# signal-a-1.net
KiCad netlist of a schematic drawn in EAGLE
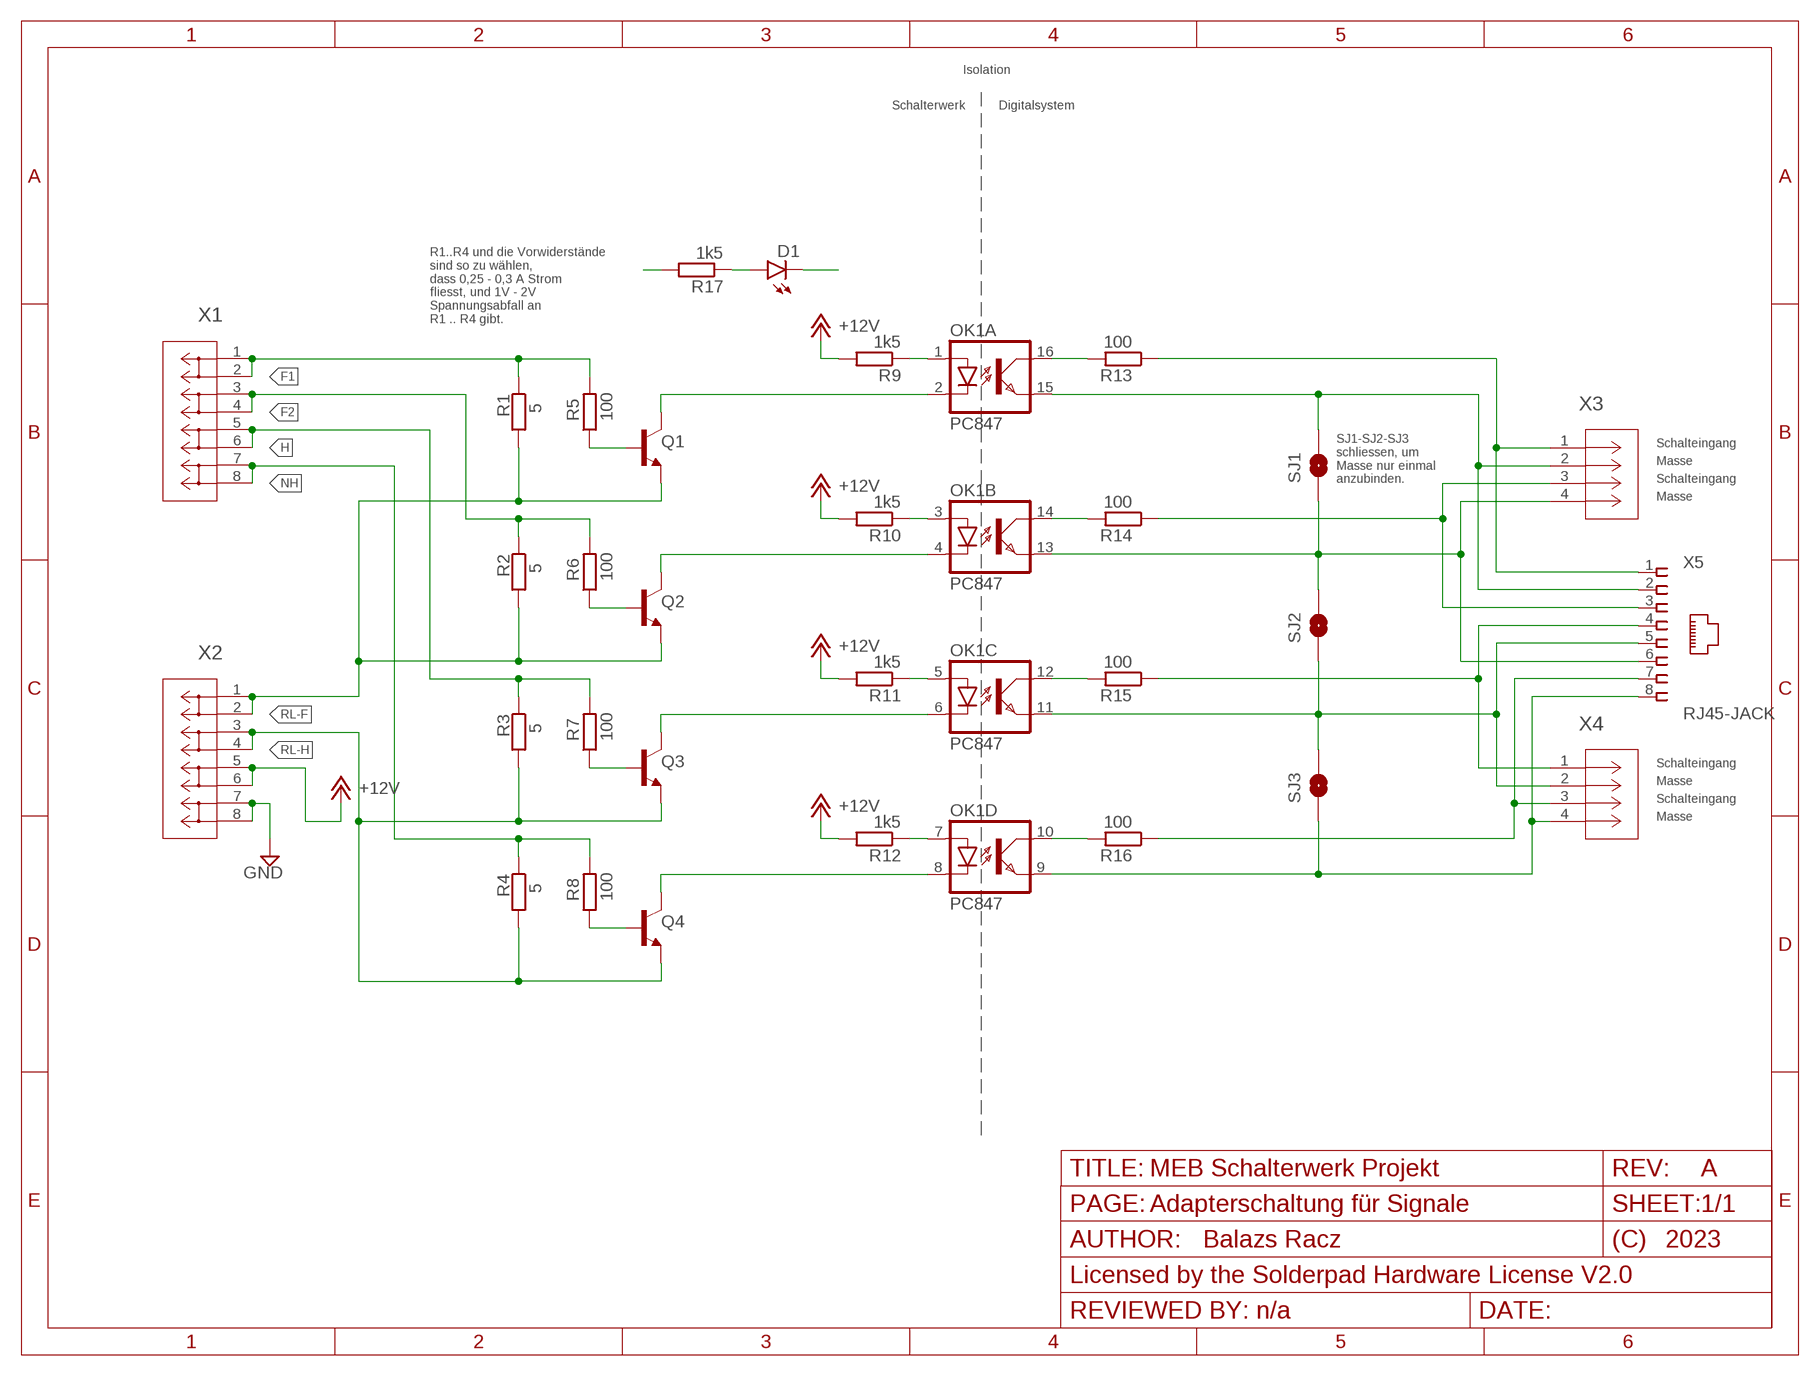
[diagram p0: schematic, sheet 1]

(export (version "E")
  (design (tool "Eeschema 10.0.6"))
  (components
    (comp (ref "D1")
      (value "LEDCHIPLED_0603")
      (footprint "eagle-import:CHIPLED_0603")
      (libsource (lib "eagle-import") (part "LEDCHIPLED_0603"))
    )
    (comp (ref "OK1")
      (value "PC847")
      (footprint "eagle-import:DIL16")
      (libsource (lib "eagle-import") (part "PC847"))
    )
    (comp (ref "Q1")
      (value "NPN-23")
      (footprint "eagle-import:SOT23")
      (libsource (lib "eagle-import") (part "NPN-23"))
    )
    (comp (ref "Q2")
      (value "NPN-23")
      (footprint "eagle-import:SOT23")
      (libsource (lib "eagle-import") (part "NPN-23"))
    )
    (comp (ref "Q3")
      (value "NPN-23")
      (footprint "eagle-import:SOT23")
      (libsource (lib "eagle-import") (part "NPN-23"))
    )
    (comp (ref "Q4")
      (value "NPN-23")
      (footprint "eagle-import:SOT23")
      (libsource (lib "eagle-import") (part "NPN-23"))
    )
    (comp (ref "R1")
      (value "5")
      (footprint "eagle-import:VTA52")
      (libsource (lib "eagle-import") (part "R-EU_VTA52"))
    )
    (comp (ref "R2")
      (value "5")
      (footprint "eagle-import:VTA52")
      (libsource (lib "eagle-import") (part "R-EU_VTA52"))
    )
    (comp (ref "R3")
      (value "5")
      (footprint "eagle-import:VTA52")
      (libsource (lib "eagle-import") (part "R-EU_VTA52"))
    )
    (comp (ref "R4")
      (value "5")
      (footprint "eagle-import:VTA52")
      (libsource (lib "eagle-import") (part "R-EU_VTA52"))
    )
    (comp (ref "R5")
      (value "100")
      (footprint "eagle-import:R0805")
      (libsource (lib "eagle-import") (part "R-EU_R0805"))
    )
    (comp (ref "R6")
      (value "100")
      (footprint "eagle-import:R0805")
      (libsource (lib "eagle-import") (part "R-EU_R0805"))
    )
    (comp (ref "R7")
      (value "100")
      (footprint "eagle-import:R0805")
      (libsource (lib "eagle-import") (part "R-EU_R0805"))
    )
    (comp (ref "R8")
      (value "100")
      (footprint "eagle-import:R0805")
      (libsource (lib "eagle-import") (part "R-EU_R0805"))
    )
    (comp (ref "R9")
      (value "1k5")
      (footprint "eagle-import:R0805")
      (libsource (lib "eagle-import") (part "R-EU_R0805"))
    )
    (comp (ref "R10")
      (value "1k5")
      (footprint "eagle-import:R0805")
      (libsource (lib "eagle-import") (part "R-EU_R0805"))
    )
    (comp (ref "R11")
      (value "1k5")
      (footprint "eagle-import:R0805")
      (libsource (lib "eagle-import") (part "R-EU_R0805"))
    )
    (comp (ref "R12")
      (value "1k5")
      (footprint "eagle-import:R0805")
      (libsource (lib "eagle-import") (part "R-EU_R0805"))
    )
    (comp (ref "R13")
      (value "100")
      (footprint "eagle-import:R0805")
      (libsource (lib "eagle-import") (part "R-EU_R0805"))
    )
    (comp (ref "R14")
      (value "100")
      (footprint "eagle-import:R0805")
      (libsource (lib "eagle-import") (part "R-EU_R0805"))
    )
    (comp (ref "R15")
      (value "100")
      (footprint "eagle-import:R0805")
      (libsource (lib "eagle-import") (part "R-EU_R0805"))
    )
    (comp (ref "R16")
      (value "100")
      (footprint "eagle-import:R0805")
      (libsource (lib "eagle-import") (part "R-EU_R0805"))
    )
    (comp (ref "R17")
      (value "1k5")
      (footprint "eagle-import:R0805")
      (libsource (lib "eagle-import") (part "R-EU_R0805"))
    )
    (comp (ref "SJ1")
      (value "SJRND2")
      (footprint "eagle-import:SJ_RND2")
      (libsource (lib "eagle-import") (part "SJRND2"))
    )
    (comp (ref "SJ2")
      (value "SJRND2")
      (footprint "eagle-import:SJ_RND2")
      (libsource (lib "eagle-import") (part "SJRND2"))
    )
    (comp (ref "SJ3")
      (value "SJRND2")
      (footprint "eagle-import:SJ_RND2")
      (libsource (lib "eagle-import") (part "SJRND2"))
    )
    (comp (ref "X1")
      (value "PHNX_4P_508CONN_1017493")
      (footprint "eagle-import:PHNX_4P_508")
      (fields
        (field (name "MANUFACTURER_PART_NUMBER") "1017505")
        (field (name "COPYRIGHT") "Copyright (C) 2023 Ultra Librarian. All rights reserved.")
      )
      (libsource (lib "eagle-import") (part "PHNX_4P_508CONN_1017493"))
    )
    (comp (ref "X2")
      (value "PHNX_4P_508CONN_1017493")
      (footprint "eagle-import:PHNX_4P_508")
      (fields
        (field (name "MANUFACTURER_PART_NUMBER") "1017505")
        (field (name "COPYRIGHT") "Copyright (C) 2023 Ultra Librarian. All rights reserved.")
      )
      (libsource (lib "eagle-import") (part "PHNX_4P_508CONN_1017493"))
    )
    (comp (ref "X3")
      (value "PHNX_4P_350CONN_1984989_PXC")
      (footprint "eagle-import:PHNX_4P_350")
      (fields
        (field (name "MANUFACTURER_PART_NUMBER") "1984989")
        (field (name "COPYRIGHT") "Copyright (C) 2023 Ultra Librarian. All rights reserved.")
      )
      (libsource (lib "eagle-import") (part "PHNX_4P_350CONN_1984989_PXC"))
    )
    (comp (ref "X4")
      (value "PHNX_4P_350CONN_1984989_PXC")
      (footprint "eagle-import:PHNX_4P_350")
      (fields
        (field (name "MANUFACTURER_PART_NUMBER") "1984989")
        (field (name "COPYRIGHT") "Copyright (C) 2023 Ultra Librarian. All rights reserved.")
      )
      (libsource (lib "eagle-import") (part "PHNX_4P_350CONN_1984989_PXC"))
    )
    (comp (ref "X5")
      (value "RJ45-JACK")
      (footprint "eagle-import:RJ45-PULSE-E5J88")
      (libsource (lib "eagle-import") (part "RJ45-JACKRJ45-PULSE-E5J00"))
    )
  )
  (nets
    (net (code "1") (name "+12V") (class "Default")
      (node (ref "R10") (pin "2") (pinfunction "2_2") (pintype "passive"))
      (node (ref "R11") (pin "2") (pinfunction "2_2") (pintype "passive"))
      (node (ref "R12") (pin "2") (pinfunction "2_2") (pintype "passive"))
      (node (ref "R9") (pin "2") (pinfunction "2_2") (pintype "passive"))
      (node (ref "X2") (pin "5") (pinfunction "5_5") (pintype "passive"))
      (node (ref "X2") (pin "6") (pinfunction "6_6") (pintype "passive"))
    )
    (net (code "2") (name "F1") (class "Default")
      (node (ref "R1") (pin "1") (pinfunction "1_1") (pintype "passive"))
      (node (ref "R5") (pin "2") (pinfunction "2_2") (pintype "passive"))
      (node (ref "X1") (pin "1") (pinfunction "1_1") (pintype "passive"))
      (node (ref "X1") (pin "2") (pinfunction "2_2") (pintype "passive"))
    )
    (net (code "3") (name "F2") (class "Default")
      (node (ref "R2") (pin "1") (pinfunction "1_1") (pintype "passive"))
      (node (ref "R6") (pin "2") (pinfunction "2_2") (pintype "passive"))
      (node (ref "X1") (pin "3") (pinfunction "3_3") (pintype "passive"))
      (node (ref "X1") (pin "4") (pinfunction "4_4") (pintype "passive"))
    )
    (net (code "4") (name "GND") (class "Default")
      (node (ref "X2") (pin "7") (pinfunction "7_7") (pintype "passive"))
      (node (ref "X2") (pin "8") (pinfunction "8_8") (pintype "passive"))
    )
    (net (code "5") (name "H") (class "Default")
      (node (ref "R3") (pin "1") (pinfunction "1_1") (pintype "passive"))
      (node (ref "R7") (pin "2") (pinfunction "2_2") (pintype "passive"))
      (node (ref "X1") (pin "5") (pinfunction "5_5") (pintype "passive"))
      (node (ref "X1") (pin "6") (pinfunction "6_6") (pintype "passive"))
    )
    (net (code "6") (name "NH") (class "Default")
      (node (ref "R4") (pin "1") (pinfunction "1_1") (pintype "passive"))
      (node (ref "R8") (pin "2") (pinfunction "2_2") (pintype "passive"))
      (node (ref "X1") (pin "7") (pinfunction "7_7") (pintype "passive"))
      (node (ref "X1") (pin "8") (pinfunction "8_8") (pintype "passive"))
    )
    (net (code "7") (name "Net-(D1-PadA)") (class "Default")
      (node (ref "D1") (pin "A") (pinfunction "A_A") (pintype "passive"))
      (node (ref "R17") (pin "1") (pinfunction "1_1") (pintype "passive"))
    )
    (net (code "8") (name "Net-(OK1A-A)") (class "Default")
      (node (ref "OK1") (pin "1") (pinfunction "A_1") (pintype "passive"))
      (node (ref "R9") (pin "1") (pinfunction "1_1") (pintype "passive"))
    )
    (net (code "9") (name "Net-(OK1A-C)") (class "Default")
      (node (ref "OK1") (pin "2") (pinfunction "C_2") (pintype "passive"))
      (node (ref "Q1") (pin "3") (pinfunction "C_3") (pintype "passive"))
    )
    (net (code "10") (name "Net-(OK1A-COL)") (class "Default")
      (node (ref "OK1") (pin "16") (pinfunction "COL_16") (pintype "passive"))
      (node (ref "R13") (pin "2") (pinfunction "2_2") (pintype "passive"))
    )
    (net (code "11") (name "Net-(OK1A-EMIT)") (class "Default")
      (node (ref "OK1") (pin "15") (pinfunction "EMIT_15") (pintype "passive"))
      (node (ref "SJ1") (pin "P$2") (pinfunction "2_P$2") (pintype "passive"))
      (node (ref "X3") (pin "2") (pinfunction "2_2") (pintype "passive"))
      (node (ref "X5") (pin "2") (pinfunction "2_2") (pintype "passive"))
    )
    (net (code "12") (name "Net-(OK1B-A)") (class "Default")
      (node (ref "OK1") (pin "3") (pinfunction "A_3") (pintype "passive"))
      (node (ref "R10") (pin "1") (pinfunction "1_1") (pintype "passive"))
    )
    (net (code "13") (name "Net-(OK1B-C)") (class "Default")
      (node (ref "OK1") (pin "4") (pinfunction "C_4") (pintype "passive"))
      (node (ref "Q2") (pin "3") (pinfunction "C_3") (pintype "passive"))
    )
    (net (code "14") (name "Net-(OK1B-COL)") (class "Default")
      (node (ref "OK1") (pin "14") (pinfunction "COL_14") (pintype "passive"))
      (node (ref "R14") (pin "2") (pinfunction "2_2") (pintype "passive"))
    )
    (net (code "15") (name "Net-(OK1B-EMIT)") (class "Default")
      (node (ref "OK1") (pin "13") (pinfunction "EMIT_13") (pintype "passive"))
      (node (ref "SJ1") (pin "P$1") (pinfunction "1_P$1") (pintype "passive"))
      (node (ref "SJ2") (pin "P$2") (pinfunction "2_P$2") (pintype "passive"))
      (node (ref "X3") (pin "4") (pinfunction "4_4") (pintype "passive"))
      (node (ref "X5") (pin "6") (pinfunction "6_6") (pintype "passive"))
    )
    (net (code "16") (name "Net-(OK1C-A)") (class "Default")
      (node (ref "OK1") (pin "5") (pinfunction "A_5") (pintype "passive"))
      (node (ref "R11") (pin "1") (pinfunction "1_1") (pintype "passive"))
    )
    (net (code "17") (name "Net-(OK1C-C)") (class "Default")
      (node (ref "OK1") (pin "6") (pinfunction "C_6") (pintype "passive"))
      (node (ref "Q3") (pin "3") (pinfunction "C_3") (pintype "passive"))
    )
    (net (code "18") (name "Net-(OK1C-COL)") (class "Default")
      (node (ref "OK1") (pin "12") (pinfunction "COL_12") (pintype "passive"))
      (node (ref "R15") (pin "2") (pinfunction "2_2") (pintype "passive"))
    )
    (net (code "19") (name "Net-(OK1C-EMIT)") (class "Default")
      (node (ref "OK1") (pin "11") (pinfunction "EMIT_11") (pintype "passive"))
      (node (ref "SJ2") (pin "P$1") (pinfunction "1_P$1") (pintype "passive"))
      (node (ref "SJ3") (pin "P$2") (pinfunction "2_P$2") (pintype "passive"))
      (node (ref "X4") (pin "2") (pinfunction "2_2") (pintype "passive"))
      (node (ref "X5") (pin "5") (pinfunction "5_5") (pintype "passive"))
    )
    (net (code "20") (name "Net-(OK1D-A)") (class "Default")
      (node (ref "OK1") (pin "7") (pinfunction "A_7") (pintype "passive"))
      (node (ref "R12") (pin "1") (pinfunction "1_1") (pintype "passive"))
    )
    (net (code "21") (name "Net-(OK1D-C)") (class "Default")
      (node (ref "OK1") (pin "8") (pinfunction "C_8") (pintype "passive"))
      (node (ref "Q4") (pin "3") (pinfunction "C_3") (pintype "passive"))
    )
    (net (code "22") (name "Net-(OK1D-COL)") (class "Default")
      (node (ref "OK1") (pin "10") (pinfunction "COL_10") (pintype "passive"))
      (node (ref "R16") (pin "2") (pinfunction "2_2") (pintype "passive"))
    )
    (net (code "23") (name "Net-(OK1D-EMIT)") (class "Default")
      (node (ref "OK1") (pin "9") (pinfunction "EMIT_9") (pintype "passive"))
      (node (ref "SJ3") (pin "P$1") (pinfunction "1_P$1") (pintype "passive"))
      (node (ref "X4") (pin "4") (pinfunction "4_4") (pintype "passive"))
      (node (ref "X5") (pin "8") (pinfunction "8_8") (pintype "passive"))
    )
    (net (code "24") (name "Net-(Q1-B)") (class "Default")
      (node (ref "Q1") (pin "1") (pinfunction "B_1") (pintype "passive"))
      (node (ref "R5") (pin "1") (pinfunction "1_1") (pintype "passive"))
    )
    (net (code "25") (name "Net-(Q2-B)") (class "Default")
      (node (ref "Q2") (pin "1") (pinfunction "B_1") (pintype "passive"))
      (node (ref "R6") (pin "1") (pinfunction "1_1") (pintype "passive"))
    )
    (net (code "26") (name "Net-(Q3-B)") (class "Default")
      (node (ref "Q3") (pin "1") (pinfunction "B_1") (pintype "passive"))
      (node (ref "R7") (pin "1") (pinfunction "1_1") (pintype "passive"))
    )
    (net (code "27") (name "Net-(Q4-B)") (class "Default")
      (node (ref "Q4") (pin "1") (pinfunction "B_1") (pintype "passive"))
      (node (ref "R8") (pin "1") (pinfunction "1_1") (pintype "passive"))
    )
    (net (code "28") (name "Net-(R13-Pad1)") (class "Default")
      (node (ref "R13") (pin "1") (pinfunction "1_1") (pintype "passive"))
      (node (ref "X3") (pin "1") (pinfunction "1_1") (pintype "passive"))
      (node (ref "X5") (pin "1") (pinfunction "1_1") (pintype "passive"))
    )
    (net (code "29") (name "Net-(R14-Pad1)") (class "Default")
      (node (ref "R14") (pin "1") (pinfunction "1_1") (pintype "passive"))
      (node (ref "X3") (pin "3") (pinfunction "3_3") (pintype "passive"))
      (node (ref "X5") (pin "3") (pinfunction "3_3") (pintype "passive"))
    )
    (net (code "30") (name "Net-(R15-Pad1)") (class "Default")
      (node (ref "R15") (pin "1") (pinfunction "1_1") (pintype "passive"))
      (node (ref "X4") (pin "1") (pinfunction "1_1") (pintype "passive"))
      (node (ref "X5") (pin "4") (pinfunction "4_4") (pintype "passive"))
    )
    (net (code "31") (name "Net-(R16-Pad1)") (class "Default")
      (node (ref "R16") (pin "1") (pinfunction "1_1") (pintype "passive"))
      (node (ref "X4") (pin "3") (pinfunction "3_3") (pintype "passive"))
      (node (ref "X5") (pin "7") (pinfunction "7_7") (pintype "passive"))
    )
    (net (code "32") (name "RL-F") (class "Default")
      (node (ref "Q1") (pin "2") (pinfunction "E_2") (pintype "passive"))
      (node (ref "Q2") (pin "2") (pinfunction "E_2") (pintype "passive"))
      (node (ref "R1") (pin "2") (pinfunction "2_2") (pintype "passive"))
      (node (ref "R2") (pin "2") (pinfunction "2_2") (pintype "passive"))
      (node (ref "X2") (pin "1") (pinfunction "1_1") (pintype "passive"))
      (node (ref "X2") (pin "2") (pinfunction "2_2") (pintype "passive"))
    )
    (net (code "33") (name "RL-H") (class "Default")
      (node (ref "Q3") (pin "2") (pinfunction "E_2") (pintype "passive"))
      (node (ref "Q4") (pin "2") (pinfunction "E_2") (pintype "passive"))
      (node (ref "R3") (pin "2") (pinfunction "2_2") (pintype "passive"))
      (node (ref "R4") (pin "2") (pinfunction "2_2") (pintype "passive"))
      (node (ref "X2") (pin "3") (pinfunction "3_3") (pintype "passive"))
      (node (ref "X2") (pin "4") (pinfunction "4_4") (pintype "passive"))
    )
    (net (code "34") (name "unconnected-(D1-PadC)") (class "Default")
      (node (ref "D1") (pin "C") (pinfunction "C_C") (pintype "passive"))
    )
    (net (code "35") (name "unconnected-(R17-Pad2)") (class "Default")
      (node (ref "R17") (pin "2") (pinfunction "2_2") (pintype "passive"))
    )
  )
)
